# Fluid_RTD_FE.net
KiCad netlist of a schematic drawn in Altium Designer
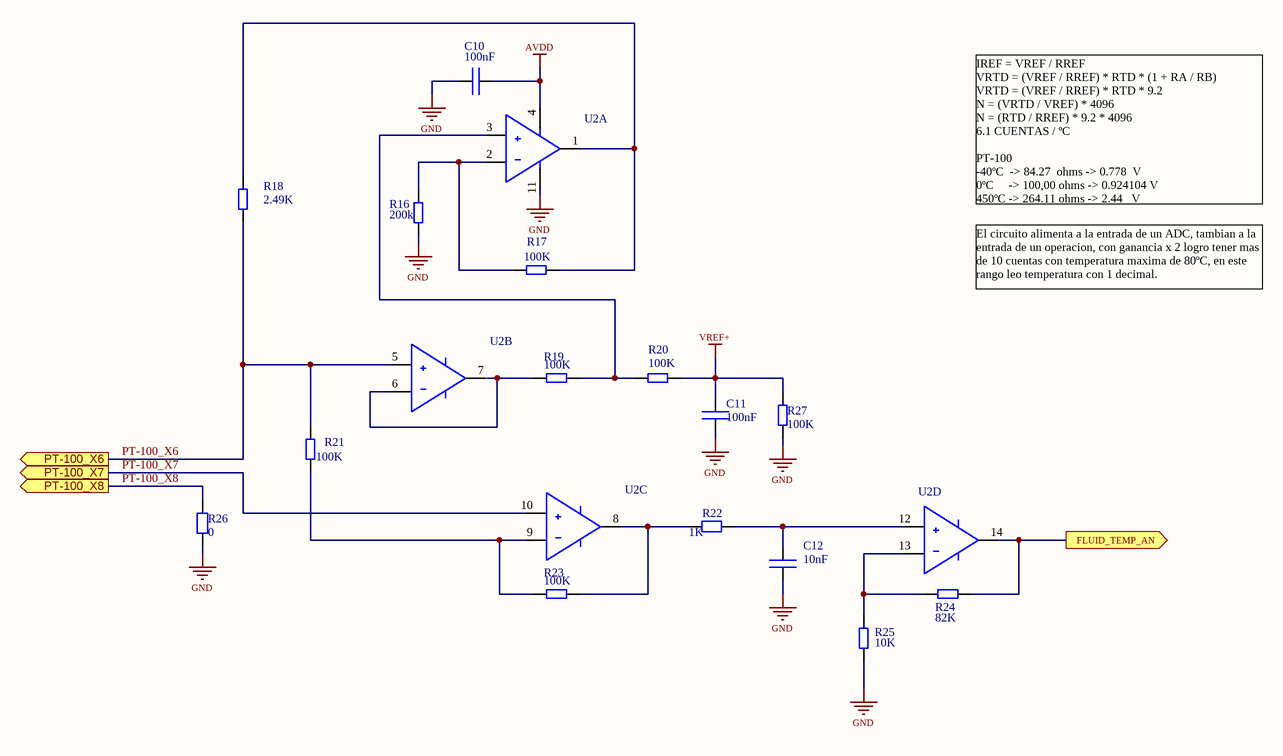
[diagram p0: Fluid_RTD_FE.SchDoc]

(export (version "E")
  (design (tool "Eeschema 10.0.6"))
  (components
    (comp (ref "C10")
      (value "100nF")
      (footprint "CAP_SM0603_YAGEOCC2_N")
      (description "CAP 100nF SM0603 X7R 50V YAGEO CC2")
      (fields
        (field (name "MANUFACTURER") "Yageo")
        (field (name "MANUFACTURER PART NUMBER") "CC0603KRX7R9BB104")
      )
      (libsource (lib "yageo") (part "CC0603KRX7R9BB104"))
    )
    (comp (ref "C11")
      (value "100nF")
      (footprint "CAP_SM0603_YAGEOCC2_N")
      (description "CAP 100nF SM0603 X7R 50V YAGEO CC2")
      (fields
        (field (name "MANUFACTURER") "Yageo")
        (field (name "MANUFACTURER PART NUMBER") "CC0603KRX7R9BB104")
      )
      (libsource (lib "yageo") (part "CC0603KRX7R9BB104"))
    )
    (comp (ref "C12")
      (value "10nF")
      (footprint "CAP_SM0603_YAGEOCC2_N")
      (description "CAP 10nF SM0603 X7R 50V YAGEO CC2")
      (fields
        (field (name "MANUFACTURER") "Yageo")
        (field (name "MANUFACTURER PART NUMBER") "CC0603KRX7R9BB103")
      )
      (libsource (lib "yageo") (part "CC0603KRX7R9BB103"))
    )
    (comp (ref "R16")
      (value "200k")
      (footprint "RES_SM0603_YAGEORC_N")
      (description "RES 200K SM0603 YAGEO RC_L")
      (fields
        (field (name "MANUFACTURER") "Yageo")
        (field (name "MANUFACTURER PART NUMBER") "RC0603FR-07200KL")
      )
      (libsource (lib "yageo") (part "RC0603FR-07200KL"))
    )
    (comp (ref "R17")
      (value "100K")
      (footprint "RES_SM0603_YAGEORC_N")
      (description "RES 100K SM0603 YAGEO RC_L")
      (fields
        (field (name "MANUFACTURER") "Yageo")
        (field (name "MANUFACTURER PART NUMBER") "RC0603FR-13100KL")
      )
      (libsource (lib "yageo") (part "RC0603FR-13100KL"))
    )
    (comp (ref "R18")
      (value "2.49K")
      (footprint "RES_SM0603_YAGEORC_N")
      (description "RES 2K49 SM0603 YAGEO RC_L")
      (fields
        (field (name "MANUFACTURER") "Yageo")
        (field (name "MANUFACTURER PART NUMBER") "RC0603FR-072K49L")
      )
      (libsource (lib "yageo") (part "RC0603FR-072K49L"))
    )
    (comp (ref "R19")
      (value "100K")
      (footprint "RES_SM0603_YAGEORC_N")
      (description "RES 100K SM0603 YAGEO RC_L")
      (fields
        (field (name "MANUFACTURER") "Yageo")
        (field (name "MANUFACTURER PART NUMBER") "RC0603FR-13100KL")
      )
      (libsource (lib "yageo") (part "RC0603FR-13100KL"))
    )
    (comp (ref "R20")
      (value "100K")
      (footprint "RES_SM0603_YAGEORC_N")
      (description "RES 100K SM0603 YAGEO RC_L")
      (fields
        (field (name "MANUFACTURER") "Yageo")
        (field (name "MANUFACTURER PART NUMBER") "RC0603FR-13100KL")
      )
      (libsource (lib "yageo") (part "RC0603FR-13100KL"))
    )
    (comp (ref "R21")
      (value "100K")
      (footprint "RES_SM0603_YAGEORC_N")
      (description "RES 100K SM0603 YAGEO RC_L")
      (fields
        (field (name "MANUFACTURER") "Yageo")
        (field (name "MANUFACTURER PART NUMBER") "RC0603FR-13100KL")
      )
      (libsource (lib "") (part "RC0603FR-13100KL_1"))
    )
    (comp (ref "R22")
      (value "1K")
      (footprint "RES_SM0603_YAGEORC_N")
      (description "RES 1K SM0603 YAGEO RC_L")
      (fields
        (field (name "MANUFACTURER") "Yageo")
        (field (name "MANUFACTURER PART NUMBER") "RC0603FR-071KL")
      )
      (libsource (lib "yageo") (part "RC0603FR-071KL"))
    )
    (comp (ref "R23")
      (value "100K")
      (footprint "RES_SM0603_YAGEORC_N")
      (description "RES 100K SM0603 YAGEO RC_L")
      (fields
        (field (name "MANUFACTURER") "Yageo")
        (field (name "MANUFACTURER PART NUMBER") "RC0603FR-13100KL")
      )
      (libsource (lib "yageo") (part "RC0603FR-13100KL"))
    )
    (comp (ref "R24")
      (value "82K")
      (footprint "RES_SM0603_YAGEORC_N")
      (description "RES 82K SM0603 YAGEO RC_L")
      (fields
        (field (name "MANUFACTURER") "Yageo")
        (field (name "MANUFACTURER PART NUMBER") "RC0603FR-0782KL")
      )
      (libsource (lib "yageo") (part "RC0603FR-0782KL"))
    )
    (comp (ref "R25")
      (value "10K")
      (footprint "RES_SM0603_YAGEORC_N")
      (description "RES 10K SM0603 YAGEO RC_L")
      (fields
        (field (name "MANUFACTURER") "Yageo")
        (field (name "MANUFACTURER PART NUMBER") "RC0603FR-0710KL")
      )
      (libsource (lib "yageo") (part "RC0603FR-0710KL"))
    )
    (comp (ref "R26")
      (value "0")
      (footprint "RES_SM0603_YAGEORC_N")
      (description "RES 0 OHMS SM0603 YAGEO RC_L")
      (fields
        (field (name "MANUFACTURER") "Yageo")
        (field (name "MANUFACTURER PART NUMBER") "RC0603FR-070RL")
      )
      (libsource (lib "yageo") (part "RC0603FR-070RL"))
    )
    (comp (ref "R27")
      (value "100K")
      (footprint "RES_SM0603_YAGEORC_N")
      (description "RES 100K SM0603 YAGEO RC_L")
      (fields
        (field (name "MANUFACTURER") "Yageo")
        (field (name "MANUFACTURER PART NUMBER") "RC0603FR-13100KL")
      )
      (libsource (lib "") (part "RC0603FR-13100KL_1"))
    )
    (comp (ref "U2")
      (value "GS8044")
      (footprint "GS8044-SR")
      (description "IC OPAMP GP 4 CIRCUIT 14SOIC")
      (fields (field (name "MANUFACTURER") "Gainsil") (field (name "MANUFACTURER PART NUMBER") "GS8044-SR"))
      (libsource (lib "flowmeet") (part "GS8044-SR"))
    )
  )
  (nets
    (net (code "1") (name "/FLUID_TEMP_AN") (class "Default")
      (node (ref "R24") (pin "2") (pintype "passive"))
      (node (ref "U2") (pin "14") (pinfunction "OUT_14") (pintype "passive"))
    )
    (net (code "2") (name "/PT-100_X6") (class "Default")
      (node (ref "R18") (pin "1") (pintype "passive"))
      (node (ref "R21") (pin "2") (pintype "passive"))
      (node (ref "U2") (pin "5") (pinfunction "IN+_5") (pintype "passive"))
    )
    (net (code "3") (name "/PT-100_X7") (class "Default")
      (node (ref "U2") (pin "10") (pinfunction "IN+_10") (pintype "passive"))
    )
    (net (code "4") (name "/PT-100_X8") (class "Default") (node (ref "R26") (pin "2") (pintype "passive")))
    (net (code "5") (name "AVDD") (class "Default")
      (node (ref "C10") (pin "1") (pintype "passive"))
      (node (ref "U2") (pin "4") (pinfunction "V+_4") (pintype "power_in"))
    )
    (net (code "6") (name "GND") (class "Default")
      (node (ref "C10") (pin "2") (pintype "passive"))
      (node (ref "C11") (pin "2") (pintype "passive"))
      (node (ref "C12") (pin "2") (pintype "passive"))
      (node (ref "R16") (pin "1") (pintype "passive"))
      (node (ref "R25") (pin "1") (pintype "passive"))
      (node (ref "R26") (pin "1") (pintype "passive"))
      (node (ref "R27") (pin "1") (pintype "passive"))
      (node (ref "U2") (pin "11") (pinfunction "GND_11") (pintype "power_in"))
    )
    (net (code "7") (name "Net-(R17-Pad2)") (class "Default")
      (node (ref "R17") (pin "2") (pintype "passive"))
      (node (ref "R18") (pin "2") (pintype "passive"))
    )
    (net (code "8") (name "Net-(U2A-IN+)") (class "Default")
      (node (ref "R19") (pin "2") (pintype "passive"))
      (node (ref "R20") (pin "1") (pintype "passive"))
      (node (ref "U2") (pin "3") (pinfunction "IN+_3") (pintype "passive"))
    )
    (net (code "9") (name "Net-(U2A-IN-)") (class "Default")
      (node (ref "R16") (pin "2") (pintype "passive"))
      (node (ref "R17") (pin "1") (pintype "passive"))
      (node (ref "U2") (pin "2") (pinfunction "IN-_2") (pintype "passive"))
    )
    (net (code "10") (name "Net-(U2B-IN-)") (class "Default")
      (node (ref "R19") (pin "1") (pintype "passive"))
      (node (ref "U2") (pin "6") (pinfunction "IN-_6") (pintype "passive"))
    )
    (net (code "11") (name "Net-(U2C-IN-)") (class "Default")
      (node (ref "R21") (pin "1") (pintype "passive"))
      (node (ref "R23") (pin "1") (pintype "passive"))
      (node (ref "U2") (pin "9") (pinfunction "IN-_9") (pintype "passive"))
    )
    (net (code "12") (name "Net-(U2C-OUT)") (class "Default")
      (node (ref "R22") (pin "1") (pintype "passive"))
      (node (ref "R23") (pin "2") (pintype "passive"))
      (node (ref "U2") (pin "8") (pinfunction "OUT_8") (pintype "passive"))
    )
    (net (code "13") (name "Net-(U2D-IN+)") (class "Default")
      (node (ref "C12") (pin "1") (pintype "passive"))
      (node (ref "R22") (pin "2") (pintype "passive"))
      (node (ref "U2") (pin "12") (pinfunction "IN+_12") (pintype "passive"))
    )
    (net (code "14") (name "Net-(U2D-IN-)") (class "Default")
      (node (ref "R24") (pin "1") (pintype "passive"))
      (node (ref "R25") (pin "2") (pintype "passive"))
      (node (ref "U2") (pin "13") (pinfunction "IN-_13") (pintype "passive"))
    )
    (net (code "15") (name "VREF+") (class "Default")
      (node (ref "C11") (pin "1") (pintype "passive"))
      (node (ref "R20") (pin "2") (pintype "passive"))
      (node (ref "R27") (pin "2") (pintype "passive"))
    )
    (net (code "16") (name "unconnected-(U2A-OUT-Pad1)") (class "Default")
      (node (ref "U2") (pin "1") (pinfunction "OUT_1") (pintype "passive"))
    )
    (net (code "17") (name "unconnected-(U2B-OUT-Pad7)") (class "Default")
      (node (ref "U2") (pin "7") (pinfunction "OUT_7") (pintype "passive"))
    )
  )
)
